# Verwarmingselement.net
KiCad netlist of a schematic drawn in Altium Designer
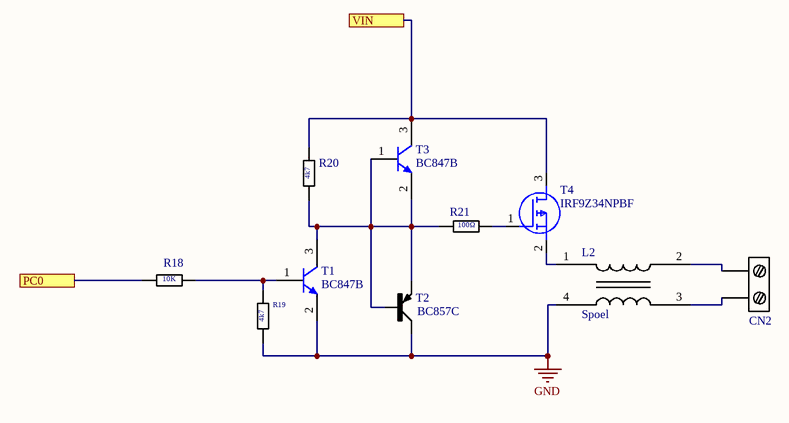
[diagram p0: Verwarmingselement.SchDoc]

(export (version "E")
  (design (tool "Eeschema 10.0.6"))
  (components
    (comp (ref "CN2")
      (value "~")
      (footprint "K1,K2,K3,K8 Printkroonsteen")
      (fields (field (name "MF") "TE Connectivity") (field (name "MP") "282837-2"))
      (libsource (lib "Soldeer Station Library") (part "K1,K2,K3,K8 Printkroonsteen"))
    )
    (comp (ref "L2")
      (value "Spoel")
      (footprint "CM2545x171B-10")
      (libsource (lib "Soldeer Station Library") (part "Common Mode Smoorspoel"))
    )
    (comp (ref "R18")
      (value "10K")
      (footprint "Resistor")
      (fields (field (name "MANUFACTURER") "Vishay Dale") (field (name "PART NUMBER") "CRCW08050000Z0EA"))
      (libsource (lib "Soldeer Station Library") (part "Resistor"))
    )
    (comp (ref "R19")
      (value "4k7")
      (footprint "Resistor")
      (fields (field (name "MANUFACTURER") "Vishay Dale") (field (name "PART NUMBER") "CRCW08050000Z0EA"))
      (libsource (lib "Soldeer Station Library") (part "Resistor"))
    )
    (comp (ref "R20")
      (value "4k7")
      (footprint "Resistor")
      (fields (field (name "MANUFACTURER") "Vishay Dale") (field (name "PART NUMBER") "CRCW08050000Z0EA"))
      (libsource (lib "Soldeer Station Library") (part "Resistor"))
    )
    (comp (ref "R21")
      (value "100Ω")
      (footprint "Resistor")
      (fields (field (name "MANUFACTURER") "Vishay Dale") (field (name "PART NUMBER") "CRCW08050000Z0EA"))
      (libsource (lib "Soldeer Station Library") (part "Resistor"))
    )
    (comp (ref "T1")
      (value "BC847B")
      (footprint "bc847b")
      (description "NPN Silicon AF Transistor, 45 V VCEO, 100 mA IC, SOT23, Reel, Green")
      (fields (field (name "MANUFACTURER") "Infineon"))
      (libsource (lib "Soldeer Station Library") (part "BC847B"))
    )
    (comp (ref "T2")
      (value "BC857C")
      (footprint "BC557C")
      (fields (field (name "MP") "BC557") (field (name "MF") "ON"))
      (libsource (lib "Soldeer Station Library") (part "BC557C"))
    )
    (comp (ref "T3")
      (value "BC847B")
      (footprint "bc847b")
      (description "NPN Silicon AF Transistor, 45 V VCEO, 100 mA IC, SOT23, Reel, Green")
      (fields (field (name "MANUFACTURER") "Infineon"))
      (libsource (lib "Soldeer Station Library") (part "BC847B"))
    )
    (comp (ref "T4")
      (value "IRF9Z34NPBF")
      (footprint "SamacSys:TO254P469X1042X1967-3P")
      (description "MOSFET (P-Channel)")
      (fields (field (name "MOUSER PART NUMBER") "942-IRF9Z34NPBF"))
      (libsource (lib "*") (part "IRF9Z34NPBF"))
    )
  )
  (nets
    (net (code "1") (name "/PC0") (class "Default")
      (node (ref "R18") (pin "1") (pinfunction "1_1") (pintype "passive"))
    )
    (net (code "2") (name "/VIN") (class "Default")
      (node (ref "R20") (pin "2") (pinfunction "2_2") (pintype "passive"))
      (node (ref "T3") (pin "3") (pinfunction "C_3") (pintype "passive"))
      (node (ref "T4") (pin "3") (pinfunction "D_3") (pintype "passive"))
    )
    (net (code "3") (name "GND") (class "Default")
      (node (ref "L2") (pin "4") (pinfunction "4_4") (pintype "passive"))
      (node (ref "R19") (pin "1") (pinfunction "1_1") (pintype "passive"))
      (node (ref "T1") (pin "2") (pinfunction "E_2") (pintype "passive"))
      (node (ref "T2") (pin "C") (pinfunction "C_C") (pintype "passive"))
    )
    (net (code "4") (name "Net-(CN2-Pad1)") (class "Default")
      (node (ref "CN2") (pin "1") (pinfunction "1_1") (pintype "passive"))
      (node (ref "L2") (pin "2") (pinfunction "2_2") (pintype "passive"))
    )
    (net (code "5") (name "Net-(CN2-Pad2)") (class "Default")
      (node (ref "CN2") (pin "2") (pinfunction "2_2") (pintype "passive"))
      (node (ref "L2") (pin "3") (pinfunction "3_3") (pintype "passive"))
    )
    (net (code "6") (name "Net-(T1-B)") (class "Default")
      (node (ref "R18") (pin "2") (pinfunction "2_2") (pintype "passive"))
      (node (ref "R19") (pin "2") (pinfunction "2_2") (pintype "passive"))
      (node (ref "T1") (pin "1") (pinfunction "B_1") (pintype "passive"))
    )
    (net (code "7") (name "Net-(T1-C)") (class "Default")
      (node (ref "R20") (pin "1") (pinfunction "1_1") (pintype "passive"))
      (node (ref "R21") (pin "1") (pinfunction "1_1") (pintype "passive"))
      (node (ref "T1") (pin "3") (pinfunction "C_3") (pintype "passive"))
      (node (ref "T2") (pin "B") (pinfunction "B_B") (pintype "passive"))
      (node (ref "T2") (pin "E") (pinfunction "E_E") (pintype "passive"))
      (node (ref "T3") (pin "1") (pinfunction "B_1") (pintype "passive"))
      (node (ref "T3") (pin "2") (pinfunction "E_2") (pintype "passive"))
    )
    (net (code "8") (name "Net-(T4-G)") (class "Default")
      (node (ref "R21") (pin "2") (pinfunction "2_2") (pintype "passive"))
      (node (ref "T4") (pin "1") (pinfunction "G_1") (pintype "passive"))
    )
    (net (code "9") (name "Net-(T4-S)") (class "Default")
      (node (ref "L2") (pin "1") (pinfunction "1_1") (pintype "passive"))
      (node (ref "T4") (pin "2") (pinfunction "S_2") (pintype "passive"))
    )
  )
)
